# Connectors.net
KiCad netlist of a schematic drawn in Altium Designer
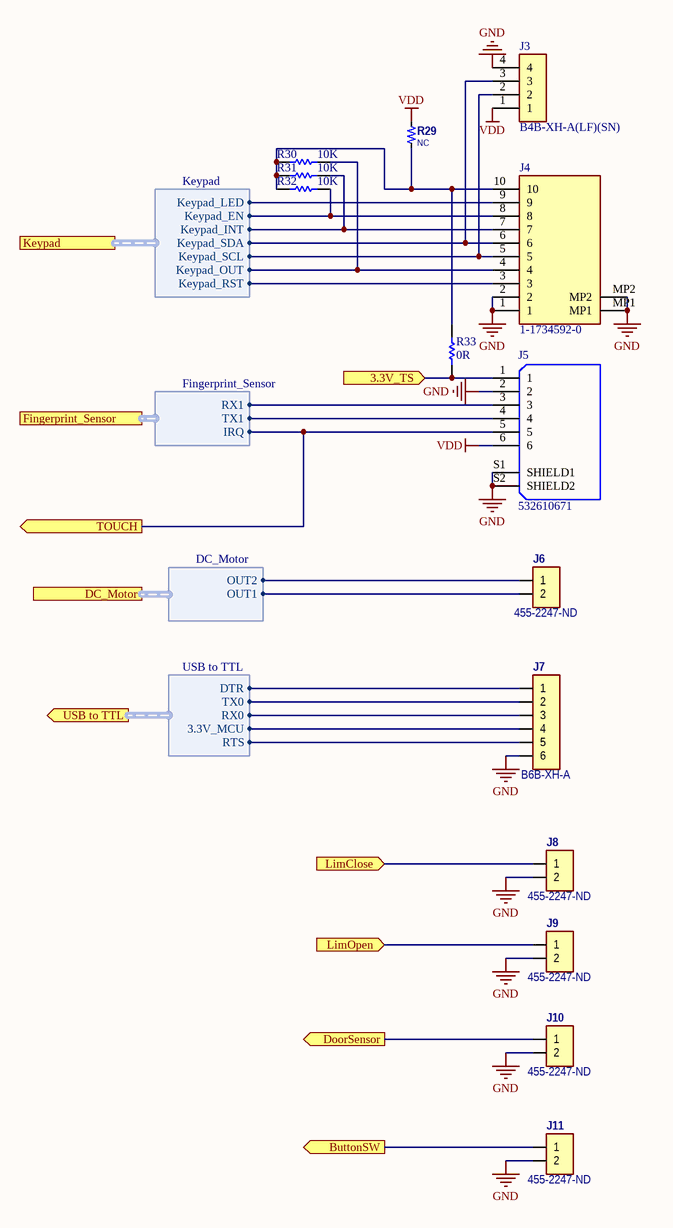
[diagram p0: Connectors.SchDoc]

(export (version "E")
  (design (tool "Eeschema 10.0.6"))
  (components
    (comp (ref "J3")
      (value "B4B-XH-A(LF)(SN)")
      (footprint "JST_B4B-XH-A(LF)(SN)")
      (description "Connector Header Through Hole 4 position 0.098 (2.50mm)")
      (fields (field (name "MF") "JST Sales"))
      (libsource (lib "Safety_Lock") (part "B4B-XH-A(LF)(SN)"))
    )
    (comp (ref "J4")
      (value "1-1734592-0")
      (footprint "117345920")
      (description "Connector")
      (fields (field (name "MOUSER PART NUMBER") "571-1-1734592-0"))
      (libsource (lib "Safety_Lock") (part "1-1734592-0"))
    )
    (comp (ref "J5")
      (value "532610671")
      (footprint "MOLEX_532610671")
      (description "Conn Shrouded Header (4 Sides) HDR 6 POS 1.25mm Solder RA Side Entry SMD PicoBladeâ„¢ T/R")
      (fields (field (name "MF") "Molex") (field (name "DIGI-KEY_PART_NUMBER") "WM7624CT-ND"))
      (libsource (lib "Safety_Lock") (part "532610671"))
    )
    (comp (ref "J6")
      (value "455-2247-ND")
      (footprint "CON_HDR1x2")
      (libsource (lib "Safety_Lock") (part "CON_HDR1x2"))
    )
    (comp (ref "J7")
      (value "B6B-XH-A")
      (footprint "CON_HDR1x6_2p50_SHRD_JST-B6B-XH-A")
      (description "CONN HEADER VERT 6POS 2.5MM")
      (fields (field (name "MANUFACTURER") "JST") (field (name "MANUFACTURER PART NUMBER") "B6BXHA(LF)(SN)"))
      (libsource (lib "Safety_Lock") (part "CON_HDR1x6_2p50_SHRD_JST_B6B-XH-A"))
    )
    (comp (ref "J8")
      (value "455-2247-ND")
      (footprint "CON_HDR1x2")
      (libsource (lib "Safety_Lock") (part "CON_HDR1x2"))
    )
    (comp (ref "J9")
      (value "455-2247-ND")
      (footprint "CON_HDR1x2")
      (libsource (lib "Safety_Lock") (part "CON_HDR1x2"))
    )
    (comp (ref "J10")
      (value "455-2247-ND")
      (footprint "CON_HDR1x2")
      (libsource (lib "Safety_Lock") (part "CON_HDR1x2"))
    )
    (comp (ref "J11")
      (value "455-2247-ND")
      (footprint "CON_HDR1x2")
      (libsource (lib "Safety_Lock") (part "CON_HDR1x2"))
    )
    (comp (ref "R29")
      (value "NC")
      (footprint "0603-R")
      (fields
        (field (name "MANUFACTURER") "Panasonic")
        (field (name "MANUFACTURER PART NUMBER") "ERJ-8GEYJ621V")
        (field (name "TOLERANCE") "5%")
      )
      (libsource (lib "Safety_Lock") (part "Res"))
    )
    (comp (ref "R30")
      (value "10K")
      (footprint "0603R")
      (description "Resistor")
      (fields (field (name "PUBLISHER") "Altium Limited"))
      (libsource (lib "Miscellaneous Devices") (part "res1"))
    )
    (comp (ref "R31")
      (value "10K")
      (footprint "0603R")
      (description "Resistor")
      (fields (field (name "PUBLISHER") "Altium Limited"))
      (libsource (lib "Miscellaneous Devices") (part "res1"))
    )
    (comp (ref "R32")
      (value "10K")
      (footprint "0603R")
      (description "Resistor")
      (fields (field (name "PUBLISHER") "Altium Limited"))
      (libsource (lib "Miscellaneous Devices") (part "res1"))
    )
    (comp (ref "R33")
      (value "0R")
      (footprint "0603R")
      (description "Resistor")
      (fields (field (name "PUBLISHER") "Altium Limited"))
      (libsource (lib "Miscellaneous Devices") (part "res1"))
    )
  )
  (nets
    (net (code "7") (name "/3.3V_MCU") (class "Default")
      (node (ref "J7") (pin "4") (pinfunction "4_4") (pintype "passive"))
    )
    (net (code "8") (name "/3.3V_TS") (class "Default")
      (node (ref "J5") (pin "1") (pinfunction "1_1") (pintype "passive"))
      (node (ref "R33") (pin "1") (pinfunction "1_1") (pintype "passive"))
    )
    (net (code "9") (name "/ButtonSW") (class "Default")
      (node (ref "J11") (pin "1") (pinfunction "1_1") (pintype "passive"))
    )
    (net (code "10") (name "/DTR") (class "Default")
      (node (ref "J7") (pin "1") (pinfunction "1_1") (pintype "passive"))
    )
    (net (code "11") (name "/DoorSensor") (class "Default")
      (node (ref "J10") (pin "1") (pinfunction "1_1") (pintype "passive"))
    )
    (net (code "12") (name "/Keypad_EN") (class "Default")
      (node (ref "J4") (pin "8") (pinfunction "8_8") (pintype "passive"))
      (node (ref "R32") (pin "2") (pinfunction "2_2") (pintype "passive"))
    )
    (net (code "13") (name "/Keypad_INT") (class "Default")
      (node (ref "J4") (pin "7") (pinfunction "7_7") (pintype "passive"))
      (node (ref "R31") (pin "2") (pinfunction "2_2") (pintype "passive"))
    )
    (net (code "14") (name "/Keypad_LED") (class "Default")
      (node (ref "J4") (pin "9") (pinfunction "9_9") (pintype "passive"))
    )
    (net (code "15") (name "/Keypad_OUT") (class "Default")
      (node (ref "J4") (pin "4") (pinfunction "4_4") (pintype "passive"))
      (node (ref "R30") (pin "2") (pinfunction "2_2") (pintype "passive"))
    )
    (net (code "16") (name "/Keypad_RST") (class "Default")
      (node (ref "J4") (pin "3") (pinfunction "3_3") (pintype "passive"))
    )
    (net (code "17") (name "/Keypad_SCL") (class "Default")
      (node (ref "J3") (pin "2") (pinfunction "2_2") (pintype "passive"))
      (node (ref "J4") (pin "5") (pinfunction "5_5") (pintype "passive"))
    )
    (net (code "18") (name "/Keypad_SDA") (class "Default")
      (node (ref "J3") (pin "3") (pinfunction "3_3") (pintype "passive"))
      (node (ref "J4") (pin "6") (pinfunction "6_6") (pintype "passive"))
    )
    (net (code "19") (name "/LimClose") (class "Default")
      (node (ref "J8") (pin "1") (pinfunction "1_1") (pintype "passive"))
    )
    (net (code "20") (name "/LimOpen") (class "Default")
      (node (ref "J9") (pin "1") (pinfunction "1_1") (pintype "passive"))
    )
    (net (code "21") (name "/OUT1") (class "Default")
      (node (ref "J6") (pin "2") (pinfunction "2_2") (pintype "passive"))
    )
    (net (code "22") (name "/OUT2") (class "Default")
      (node (ref "J6") (pin "1") (pinfunction "1_1") (pintype "passive"))
    )
    (net (code "23") (name "/RTS") (class "Default")
      (node (ref "J7") (pin "5") (pinfunction "5_5") (pintype "passive"))
    )
    (net (code "24") (name "/RX0") (class "Default")
      (node (ref "J7") (pin "3") (pinfunction "3_3") (pintype "passive"))
    )
    (net (code "25") (name "/RX1") (class "Default")
      (node (ref "J5") (pin "3") (pinfunction "3_3") (pintype "passive"))
    )
    (net (code "26") (name "/TOUCH") (class "Default")
      (node (ref "J5") (pin "5") (pinfunction "5_5") (pintype "passive"))
    )
    (net (code "27") (name "/TX0") (class "Default")
      (node (ref "J7") (pin "2") (pinfunction "2_2") (pintype "passive"))
    )
    (net (code "28") (name "/TX1") (class "Default")
      (node (ref "J5") (pin "4") (pinfunction "4_4") (pintype "passive"))
    )
    (net (code "33") (name "GND") (class "Default")
      (node (ref "J10") (pin "2") (pinfunction "2_2") (pintype "passive"))
      (node (ref "J11") (pin "2") (pinfunction "2_2") (pintype "passive"))
      (node (ref "J3") (pin "4") (pinfunction "4_4") (pintype "passive"))
      (node (ref "J4") (pin "1") (pinfunction "1_1") (pintype "passive"))
      (node (ref "J4") (pin "2") (pinfunction "2_2") (pintype "passive"))
      (node (ref "J4") (pin "MP1") (pinfunction "MP1_MP1") (pintype "passive"))
      (node (ref "J4") (pin "MP2") (pinfunction "MP2_MP2") (pintype "passive"))
      (node (ref "J5") (pin "2") (pinfunction "2_2") (pintype "passive"))
      (node (ref "J5") (pin "S1") (pinfunction "SHIELD1_S1") (pintype "passive"))
      (node (ref "J5") (pin "S2") (pinfunction "SHIELD2_S2") (pintype "passive"))
      (node (ref "J7") (pin "6") (pinfunction "6_6") (pintype "passive"))
      (node (ref "J8") (pin "2") (pinfunction "2_2") (pintype "passive"))
      (node (ref "J9") (pin "2") (pinfunction "2_2") (pintype "passive"))
    )
    (net (code "34") (name "Net-(J4-Pad10)") (class "Default")
      (node (ref "J4") (pin "10") (pinfunction "10_10") (pintype "passive"))
      (node (ref "R29") (pin "1") (pinfunction "1_1") (pintype "passive"))
      (node (ref "R30") (pin "1") (pinfunction "1_1") (pintype "passive"))
      (node (ref "R31") (pin "1") (pinfunction "1_1") (pintype "passive"))
      (node (ref "R32") (pin "1") (pinfunction "1_1") (pintype "passive"))
      (node (ref "R33") (pin "2") (pinfunction "2_2") (pintype "passive"))
    )
    (net (code "35") (name "VDD") (class "Default")
      (node (ref "J3") (pin "1") (pinfunction "1_1") (pintype "passive"))
      (node (ref "J5") (pin "6") (pinfunction "6_6") (pintype "passive"))
      (node (ref "R29") (pin "2") (pinfunction "2_2") (pintype "passive"))
    )
  )
)
